# Power_Board_Schematic.net
KiCad netlist of a schematic drawn in Altium Designer
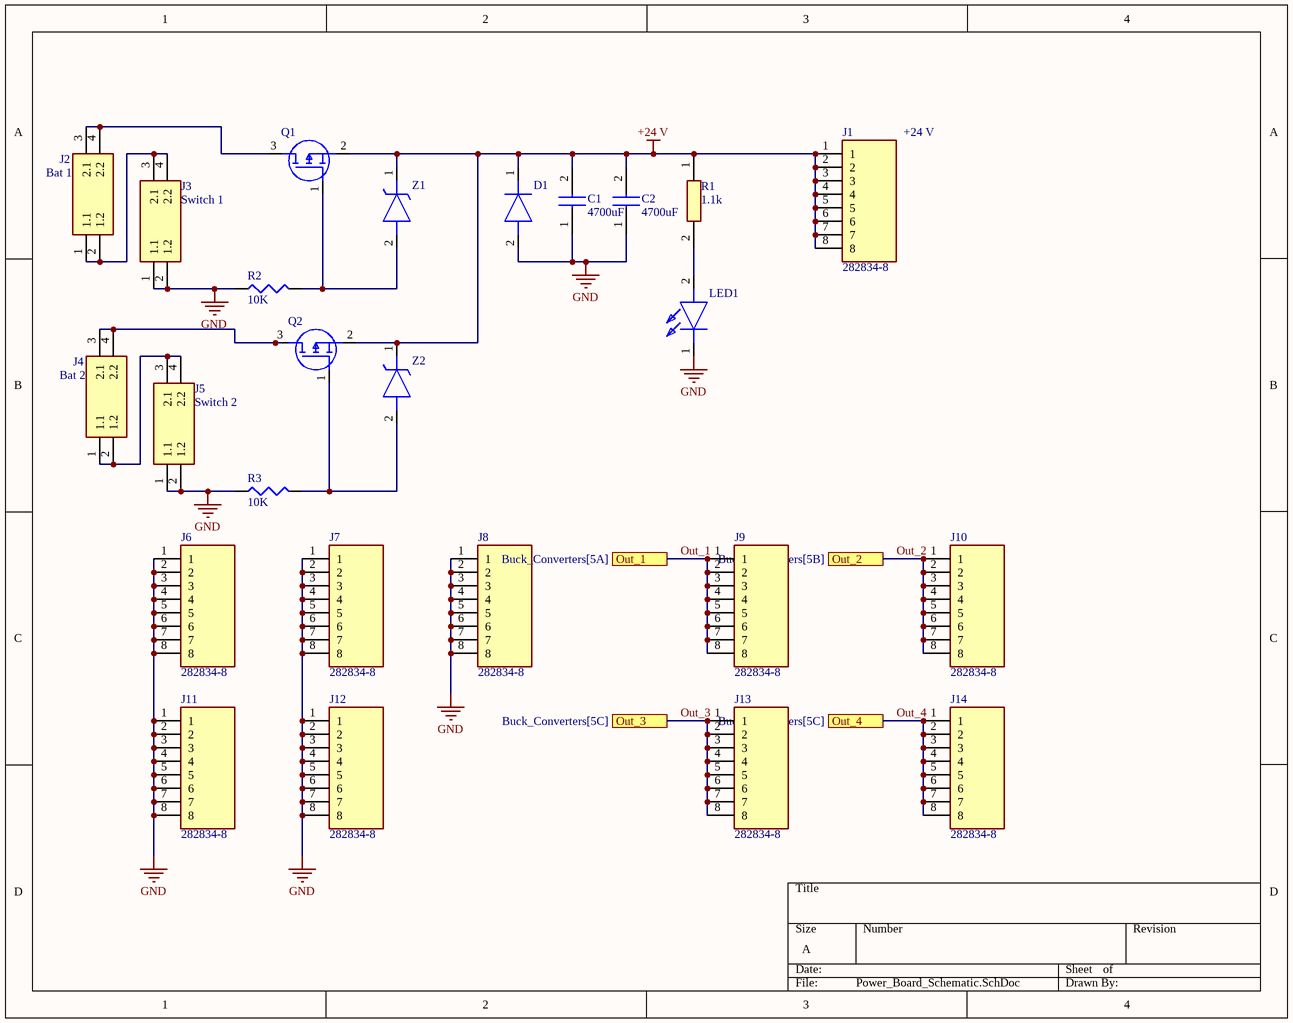
[diagram p0: Power_Board_Schematic.SchDoc]

(export (version "E")
  (design (tool "Eeschema 10.0.6"))
  (components
    (comp (ref "C1")
      (value "4700uF")
      (footprint "SamacSys:CAPPRD1000W80D2200H4100")
      (description "Capacitor")
      (fields
        (field (name "MANUFACTURER_PART_NUMBER") "860010683032")
        (field (name "MOUSER PART NUMBER") "710-860010683032")
      )
      (libsource (lib "*") (part "860010683032"))
    )
    (comp (ref "C2")
      (value "4700uF")
      (footprint "SamacSys:CAPPRD1000W80D2200H4100")
      (description "Capacitor")
      (fields
        (field (name "MANUFACTURER_PART_NUMBER") "860010683032")
        (field (name "MOUSER PART NUMBER") "710-860010683032")
      )
      (libsource (lib "*") (part "860010683032"))
    )
    (comp (ref "D1")
      (value "SZ1.5SMC36AT3G")
      (footprint "SamacSys:DIOM7958X256N")
      (description "Diode")
      (fields (field (name "MOUSER PART NUMBER") "863-SZ1.5SMC36AT3G"))
      (libsource (lib "*") (part "SZ1.5SMC36AT3G"))
    )
    (comp (ref "J1")
      (value "282834-8")
      (footprint "SamacSys:2828348")
      (description "Connector")
      (fields (field (name "MOUSER PART NUMBER") "571-282834-8"))
      (libsource (lib "*") (part "282834-8"))
    )
    (comp (ref "J2")
      (value "Bat 1")
      (footprint "SamacSys:42820-2XXY_1")
      (description "Connector")
      (fields
        (field (name "MANUFACTURER_PART_NUMBER") "42820-2214")
        (field (name "MOUSER PART NUMBER") "538-42820-2214")
      )
      (libsource (lib "*") (part "42820-2214"))
    )
    (comp (ref "J3")
      (value "Switch 1")
      (footprint "SamacSys:42820-2XXY_1")
      (description "Connector")
      (fields
        (field (name "MANUFACTURER_PART_NUMBER") "42820-2214")
        (field (name "MOUSER PART NUMBER") "538-42820-2214")
      )
      (libsource (lib "*") (part "42820-2214"))
    )
    (comp (ref "J4")
      (value "Bat 2")
      (footprint "SamacSys:42820-2XXY_1")
      (description "Connector")
      (fields
        (field (name "MANUFACTURER_PART_NUMBER") "42820-2214")
        (field (name "MOUSER PART NUMBER") "538-42820-2214")
      )
      (libsource (lib "*") (part "42820-2214"))
    )
    (comp (ref "J5")
      (value "Switch 2")
      (footprint "SamacSys:42820-2XXY_1")
      (description "Connector")
      (fields
        (field (name "MANUFACTURER_PART_NUMBER") "42820-2214")
        (field (name "MOUSER PART NUMBER") "538-42820-2214")
      )
      (libsource (lib "*") (part "42820-2214"))
    )
    (comp (ref "J6")
      (value "282834-8")
      (footprint "SamacSys:2828348")
      (description "Connector")
      (fields (field (name "MOUSER PART NUMBER") "571-282834-8"))
      (libsource (lib "*") (part "282834-8"))
    )
    (comp (ref "J7")
      (value "282834-8")
      (footprint "SamacSys:2828348")
      (description "Connector")
      (fields (field (name "MOUSER PART NUMBER") "571-282834-8"))
      (libsource (lib "*") (part "282834-8"))
    )
    (comp (ref "J8")
      (value "282834-8")
      (footprint "SamacSys:2828348")
      (description "Connector")
      (fields (field (name "MOUSER PART NUMBER") "571-282834-8"))
      (libsource (lib "*") (part "282834-8"))
    )
    (comp (ref "J9")
      (value "282834-8")
      (footprint "SamacSys:2828348")
      (description "Connector")
      (fields (field (name "MOUSER PART NUMBER") "571-282834-8"))
      (libsource (lib "*") (part "282834-8"))
    )
    (comp (ref "J10")
      (value "282834-8")
      (footprint "SamacSys:2828348")
      (description "Connector")
      (fields (field (name "MOUSER PART NUMBER") "571-282834-8"))
      (libsource (lib "*") (part "282834-8"))
    )
    (comp (ref "J11")
      (value "282834-8")
      (footprint "SamacSys:2828348")
      (description "Connector")
      (fields (field (name "MOUSER PART NUMBER") "571-282834-8"))
      (libsource (lib "*") (part "282834-8"))
    )
    (comp (ref "J12")
      (value "282834-8")
      (footprint "SamacSys:2828348")
      (description "Connector")
      (fields (field (name "MOUSER PART NUMBER") "571-282834-8"))
      (libsource (lib "*") (part "282834-8"))
    )
    (comp (ref "J13")
      (value "282834-8")
      (footprint "SamacSys:2828348")
      (description "Connector")
      (fields (field (name "MOUSER PART NUMBER") "571-282834-8"))
      (libsource (lib "*") (part "282834-8"))
    )
    (comp (ref "J14")
      (value "282834-8")
      (footprint "SamacSys:2828348")
      (description "Connector")
      (fields (field (name "MOUSER PART NUMBER") "571-282834-8"))
      (libsource (lib "*") (part "282834-8"))
    )
    (comp (ref "LED1")
      (value "CMD15-21VYC_TR8")
      (footprint "SamacSys:LEDC3215X130N")
      (description "LED")
      (fields
        (field (name "MANUFACTURER_PART_NUMBER") "CMD15-21VYC/TR8")
        (field (name "MOUSER PART NUMBER") "606-CMD15-21VYC")
      )
      (libsource (lib "*") (part "CMD15-21VYC_TR8"))
    )
    (comp (ref "Q1")
      (value "FQB47P06TM-AM002")
      (footprint "SamacSys:FFSB0865BF085")
      (description "MOSFET (P-Channel)")
      (fields (field (name "MOUSER PART NUMBER") "512-FQB47P06TM_AM002"))
      (libsource (lib "*") (part "FQB47P06TM-AM002"))
    )
    (comp (ref "Q2")
      (value "FQB47P06TM-AM002")
      (footprint "SamacSys:FFSB0865BF085")
      (description "MOSFET (P-Channel)")
      (fields (field (name "MOUSER PART NUMBER") "512-FQB47P06TM_AM002"))
      (libsource (lib "*") (part "FQB47P06TM-AM002"))
    )
    (comp (ref "R1")
      (value "1.1k")
      (footprint "SamacSys:RESC5025X71N")
      (description "SMD 3/4watt 1.1Kohms 1% 100ppm")
      (fields (field (name "MANUFACTURER_PART_NUMBER") "CRCW20101K10FKEF"))
      (libsource (lib "*") (part "CRCW20101K10FKEF"))
    )
    (comp (ref "R2")
      (value "10K")
      (footprint "1206")
      (description "Res Thick Film 1206 18K Ohm 5% 1/3W ±200ppm/°C Molded SMD SMD Punched Carrier T/R")
      (fields
        (field (name "MANUFACTURER") "Panasonic")
        (field (name "MANUFACTURER PART NUMBER") "ERJ-P08J183V")
      )
      (libsource (lib "PB_SchLib") (part "ERJ-P08J183V"))
    )
    (comp (ref "R3")
      (value "10K")
      (footprint "1206")
      (description "Res Thick Film 1206 18K Ohm 5% 1/3W ±200ppm/°C Molded SMD SMD Punched Carrier T/R")
      (fields
        (field (name "MANUFACTURER") "Panasonic")
        (field (name "MANUFACTURER PART NUMBER") "ERJ-P08J183V")
      )
      (libsource (lib "PB_SchLib") (part "ERJ-P08J183V"))
    )
    (comp (ref "Z1")
      (value "SZ1SMB5925BT3G")
      (footprint "SamacSys:DIOM5436X247N")
      (description "Zener Diode")
      (fields (field (name "MOUSER PART NUMBER") "863-SZ1SMB5925BT3G"))
      (libsource (lib "*") (part "SZ1SMB5925BT3G"))
    )
    (comp (ref "Z2")
      (value "SZ1SMB5925BT3G")
      (footprint "SamacSys:DIOM5436X247N")
      (description "Zener Diode")
      (fields (field (name "MOUSER PART NUMBER") "863-SZ1SMB5925BT3G"))
      (libsource (lib "*") (part "SZ1SMB5925BT3G"))
    )
  )
  (nets
    (net (code "1") (name "+24 V") (class "Default")
      (node (ref "C1") (pin "2") (pinfunction "-_2") (pintype "power_in"))
      (node (ref "C2") (pin "2") (pinfunction "-_2") (pintype "power_in"))
      (node (ref "D1") (pin "1") (pinfunction "K_1") (pintype "passive"))
      (node (ref "J1") (pin "1") (pinfunction "1_1") (pintype "passive"))
      (node (ref "J1") (pin "2") (pinfunction "2_2") (pintype "passive"))
      (node (ref "J1") (pin "3") (pinfunction "3_3") (pintype "passive"))
      (node (ref "J1") (pin "4") (pinfunction "4_4") (pintype "passive"))
      (node (ref "J1") (pin "5") (pinfunction "5_5") (pintype "passive"))
      (node (ref "J1") (pin "6") (pinfunction "6_6") (pintype "passive"))
      (node (ref "J1") (pin "7") (pinfunction "7_7") (pintype "passive"))
      (node (ref "J1") (pin "8") (pinfunction "8_8") (pintype "passive"))
      (node (ref "Q1") (pin "2") (pinfunction "S_2") (pintype "passive"))
      (node (ref "Q2") (pin "2") (pinfunction "S_2") (pintype "passive"))
      (node (ref "R1") (pin "1") (pinfunction "1_1") (pintype "passive"))
      (node (ref "Z1") (pin "1") (pinfunction "K_1") (pintype "passive"))
      (node (ref "Z2") (pin "1") (pinfunction "K_1") (pintype "passive"))
    )
    (net (code "2") (name "/Out_1") (class "Default")
      (node (ref "J9") (pin "1") (pinfunction "1_1") (pintype "passive"))
      (node (ref "J9") (pin "2") (pinfunction "2_2") (pintype "passive"))
      (node (ref "J9") (pin "3") (pinfunction "3_3") (pintype "passive"))
      (node (ref "J9") (pin "4") (pinfunction "4_4") (pintype "passive"))
      (node (ref "J9") (pin "5") (pinfunction "5_5") (pintype "passive"))
      (node (ref "J9") (pin "6") (pinfunction "6_6") (pintype "passive"))
      (node (ref "J9") (pin "7") (pinfunction "7_7") (pintype "passive"))
      (node (ref "J9") (pin "8") (pinfunction "8_8") (pintype "passive"))
    )
    (net (code "3") (name "/Out_2") (class "Default")
      (node (ref "J10") (pin "1") (pinfunction "1_1") (pintype "passive"))
      (node (ref "J10") (pin "2") (pinfunction "2_2") (pintype "passive"))
      (node (ref "J10") (pin "3") (pinfunction "3_3") (pintype "passive"))
      (node (ref "J10") (pin "4") (pinfunction "4_4") (pintype "passive"))
      (node (ref "J10") (pin "5") (pinfunction "5_5") (pintype "passive"))
      (node (ref "J10") (pin "6") (pinfunction "6_6") (pintype "passive"))
      (node (ref "J10") (pin "7") (pinfunction "7_7") (pintype "passive"))
      (node (ref "J10") (pin "8") (pinfunction "8_8") (pintype "passive"))
    )
    (net (code "4") (name "/Out_3") (class "Default")
      (node (ref "J13") (pin "1") (pinfunction "1_1") (pintype "passive"))
      (node (ref "J13") (pin "2") (pinfunction "2_2") (pintype "passive"))
      (node (ref "J13") (pin "3") (pinfunction "3_3") (pintype "passive"))
      (node (ref "J13") (pin "4") (pinfunction "4_4") (pintype "passive"))
      (node (ref "J13") (pin "5") (pinfunction "5_5") (pintype "passive"))
      (node (ref "J13") (pin "6") (pinfunction "6_6") (pintype "passive"))
      (node (ref "J13") (pin "7") (pinfunction "7_7") (pintype "passive"))
      (node (ref "J13") (pin "8") (pinfunction "8_8") (pintype "passive"))
    )
    (net (code "5") (name "/Out_4") (class "Default")
      (node (ref "J14") (pin "1") (pinfunction "1_1") (pintype "passive"))
      (node (ref "J14") (pin "2") (pinfunction "2_2") (pintype "passive"))
      (node (ref "J14") (pin "3") (pinfunction "3_3") (pintype "passive"))
      (node (ref "J14") (pin "4") (pinfunction "4_4") (pintype "passive"))
      (node (ref "J14") (pin "5") (pinfunction "5_5") (pintype "passive"))
      (node (ref "J14") (pin "6") (pinfunction "6_6") (pintype "passive"))
      (node (ref "J14") (pin "7") (pinfunction "7_7") (pintype "passive"))
      (node (ref "J14") (pin "8") (pinfunction "8_8") (pintype "passive"))
    )
    (net (code "6") (name "GND") (class "Default")
      (node (ref "C1") (pin "1") (pinfunction "+_1") (pintype "power_in"))
      (node (ref "C2") (pin "1") (pinfunction "+_1") (pintype "power_in"))
      (node (ref "D1") (pin "2") (pinfunction "A_2") (pintype "passive"))
      (node (ref "J11") (pin "1") (pinfunction "1_1") (pintype "passive"))
      (node (ref "J11") (pin "2") (pinfunction "2_2") (pintype "passive"))
      (node (ref "J11") (pin "3") (pinfunction "3_3") (pintype "passive"))
      (node (ref "J11") (pin "4") (pinfunction "4_4") (pintype "passive"))
      (node (ref "J11") (pin "5") (pinfunction "5_5") (pintype "passive"))
      (node (ref "J11") (pin "6") (pinfunction "6_6") (pintype "passive"))
      (node (ref "J11") (pin "7") (pinfunction "7_7") (pintype "passive"))
      (node (ref "J11") (pin "8") (pinfunction "8_8") (pintype "passive"))
      (node (ref "J12") (pin "1") (pinfunction "1_1") (pintype "passive"))
      (node (ref "J12") (pin "2") (pinfunction "2_2") (pintype "passive"))
      (node (ref "J12") (pin "3") (pinfunction "3_3") (pintype "passive"))
      (node (ref "J12") (pin "4") (pinfunction "4_4") (pintype "passive"))
      (node (ref "J12") (pin "5") (pinfunction "5_5") (pintype "passive"))
      (node (ref "J12") (pin "6") (pinfunction "6_6") (pintype "passive"))
      (node (ref "J12") (pin "7") (pinfunction "7_7") (pintype "passive"))
      (node (ref "J12") (pin "8") (pinfunction "8_8") (pintype "passive"))
      (node (ref "J3") (pin "1") (pinfunction "1.1_1") (pintype "passive"))
      (node (ref "J3") (pin "2") (pinfunction "1.2_2") (pintype "passive"))
      (node (ref "J5") (pin "1") (pinfunction "1.1_1") (pintype "passive"))
      (node (ref "J5") (pin "2") (pinfunction "1.2_2") (pintype "passive"))
      (node (ref "J6") (pin "1") (pinfunction "1_1") (pintype "passive"))
      (node (ref "J6") (pin "2") (pinfunction "2_2") (pintype "passive"))
      (node (ref "J6") (pin "3") (pinfunction "3_3") (pintype "passive"))
      (node (ref "J6") (pin "4") (pinfunction "4_4") (pintype "passive"))
      (node (ref "J6") (pin "5") (pinfunction "5_5") (pintype "passive"))
      (node (ref "J6") (pin "6") (pinfunction "6_6") (pintype "passive"))
      (node (ref "J6") (pin "7") (pinfunction "7_7") (pintype "passive"))
      (node (ref "J6") (pin "8") (pinfunction "8_8") (pintype "passive"))
      (node (ref "J7") (pin "1") (pinfunction "1_1") (pintype "passive"))
      (node (ref "J7") (pin "2") (pinfunction "2_2") (pintype "passive"))
      (node (ref "J7") (pin "3") (pinfunction "3_3") (pintype "passive"))
      (node (ref "J7") (pin "4") (pinfunction "4_4") (pintype "passive"))
      (node (ref "J7") (pin "5") (pinfunction "5_5") (pintype "passive"))
      (node (ref "J7") (pin "6") (pinfunction "6_6") (pintype "passive"))
      (node (ref "J7") (pin "7") (pinfunction "7_7") (pintype "passive"))
      (node (ref "J7") (pin "8") (pinfunction "8_8") (pintype "passive"))
      (node (ref "J8") (pin "1") (pinfunction "1_1") (pintype "passive"))
      (node (ref "J8") (pin "2") (pinfunction "2_2") (pintype "passive"))
      (node (ref "J8") (pin "3") (pinfunction "3_3") (pintype "passive"))
      (node (ref "J8") (pin "4") (pinfunction "4_4") (pintype "passive"))
      (node (ref "J8") (pin "5") (pinfunction "5_5") (pintype "passive"))
      (node (ref "J8") (pin "6") (pinfunction "6_6") (pintype "passive"))
      (node (ref "J8") (pin "7") (pinfunction "7_7") (pintype "passive"))
      (node (ref "J8") (pin "8") (pinfunction "8_8") (pintype "passive"))
      (node (ref "LED1") (pin "1") (pinfunction "K_1") (pintype "passive"))
      (node (ref "R2") (pin "1") (pinfunction "1_1") (pintype "passive"))
      (node (ref "R3") (pin "1") (pinfunction "1_1") (pintype "passive"))
    )
    (net (code "7") (name "Net-(J2-1.1)") (class "Default")
      (node (ref "J2") (pin "1") (pinfunction "1.1_1") (pintype "passive"))
      (node (ref "J2") (pin "2") (pinfunction "1.2_2") (pintype "passive"))
      (node (ref "J3") (pin "3") (pinfunction "2.1_3") (pintype "passive"))
      (node (ref "J3") (pin "4") (pinfunction "2.2_4") (pintype "passive"))
    )
    (net (code "8") (name "Net-(J2-2.1)") (class "Default")
      (node (ref "J2") (pin "3") (pinfunction "2.1_3") (pintype "passive"))
      (node (ref "J2") (pin "4") (pinfunction "2.2_4") (pintype "passive"))
      (node (ref "Q1") (pin "3") (pinfunction "D_3") (pintype "passive"))
    )
    (net (code "9") (name "Net-(J4-1.1)") (class "Default")
      (node (ref "J4") (pin "1") (pinfunction "1.1_1") (pintype "passive"))
      (node (ref "J4") (pin "2") (pinfunction "1.2_2") (pintype "passive"))
      (node (ref "J5") (pin "3") (pinfunction "2.1_3") (pintype "passive"))
      (node (ref "J5") (pin "4") (pinfunction "2.2_4") (pintype "passive"))
    )
    (net (code "10") (name "Net-(J4-2.1)") (class "Default")
      (node (ref "J4") (pin "3") (pinfunction "2.1_3") (pintype "passive"))
      (node (ref "J4") (pin "4") (pinfunction "2.2_4") (pintype "passive"))
      (node (ref "Q2") (pin "3") (pinfunction "D_3") (pintype "passive"))
    )
    (net (code "11") (name "Net-(LED1-A)") (class "Default")
      (node (ref "LED1") (pin "2") (pinfunction "A_2") (pintype "passive"))
      (node (ref "R1") (pin "2") (pinfunction "2_2") (pintype "passive"))
    )
    (net (code "12") (name "Net-(Q1-G)") (class "Default")
      (node (ref "Q1") (pin "1") (pinfunction "G_1") (pintype "passive"))
      (node (ref "R2") (pin "2") (pinfunction "2_2") (pintype "passive"))
      (node (ref "Z1") (pin "2") (pinfunction "A_2") (pintype "passive"))
    )
    (net (code "13") (name "Net-(Q2-G)") (class "Default")
      (node (ref "Q2") (pin "1") (pinfunction "G_1") (pintype "passive"))
      (node (ref "R3") (pin "2") (pinfunction "2_2") (pintype "passive"))
      (node (ref "Z2") (pin "2") (pinfunction "A_2") (pintype "passive"))
    )
  )
)
